# stonyman-breakout-adc.net
KiCad netlist of a schematic drawn in EAGLE
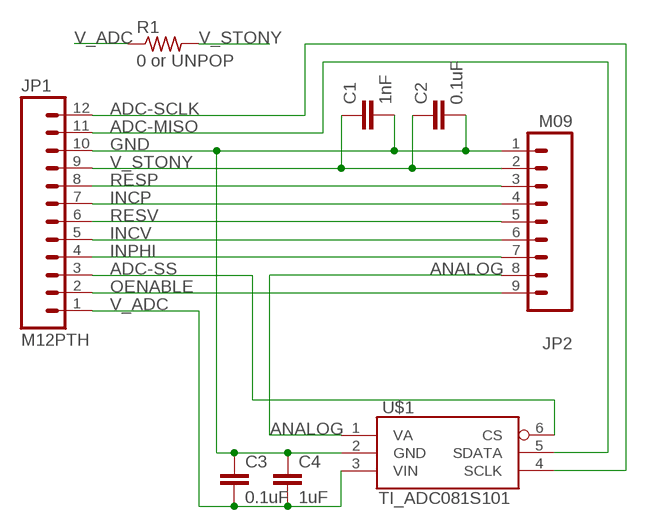
[diagram p0: schematic, sheet 1]

(export (version "E")
  (design (tool "Eeschema 10.0.6"))
  (components
    (comp (ref "C1")
      (value "1nF")
      (footprint "eagle-import:C0603")
      (libsource (lib "eagle-import") (part "C-EUC0603"))
    )
    (comp (ref "C2")
      (value "0.1uF")
      (footprint "eagle-import:C0603")
      (libsource (lib "eagle-import") (part "C-EUC0603"))
    )
    (comp (ref "C3")
      (value "0.1uF")
      (footprint "eagle-import:C0603")
      (libsource (lib "eagle-import") (part "C-EUC0603"))
    )
    (comp (ref "C4")
      (value "1uF")
      (footprint "eagle-import:C0603")
      (libsource (lib "eagle-import") (part "C-EUC0603"))
    )
    (comp (ref "JP1")
      (value "M12PTH")
      (footprint "eagle-import:1X12")
      (libsource (lib "eagle-import") (part "M12PTH"))
    )
    (comp (ref "JP2")
      (value "M09")
      (footprint "eagle-import:1X09")
      (libsource (lib "eagle-import") (part "M09"))
    )
    (comp (ref "R1")
      (value "0 or UNPOP")
      (footprint "eagle-import:R0603")
      (libsource (lib "eagle-import") (part "R-US_R0603"))
    )
    (comp (ref "U$1")
      (value "TI_ADC081S101")
      (footprint "eagle-import:SOT23-6")
      (libsource (lib "eagle-import") (part "TI_ADC081S101"))
    )
  )
  (nets
    (net (code "1") (name "/ADC-MISO") (class "Default")
      (node (ref "JP1") (pin "11") (pinfunction "11_11") (pintype "passive"))
      (node (ref "U$1") (pin "5") (pinfunction "SDATA_5") (pintype "bidirectional"))
    )
    (net (code "2") (name "/ADC-SCLK") (class "Default")
      (node (ref "JP1") (pin "12") (pinfunction "12_12") (pintype "passive"))
      (node (ref "U$1") (pin "4") (pinfunction "SCLK_4") (pintype "bidirectional"))
    )
    (net (code "3") (name "/ADC-SS") (class "Default")
      (node (ref "JP1") (pin "3") (pinfunction "3_3") (pintype "passive"))
      (node (ref "U$1") (pin "6") (pinfunction "CS_6") (pintype "bidirectional"))
    )
    (net (code "4") (name "/ANALOG") (class "Default")
      (node (ref "JP2") (pin "8") (pinfunction "8_8") (pintype "passive"))
      (node (ref "U$1") (pin "1") (pinfunction "VA_1") (pintype "bidirectional"))
    )
    (net (code "5") (name "/GND") (class "Default")
      (node (ref "C1") (pin "2") (pinfunction "2_2") (pintype "passive"))
      (node (ref "C2") (pin "2") (pinfunction "2_2") (pintype "passive"))
      (node (ref "C3") (pin "1") (pinfunction "1_1") (pintype "passive"))
      (node (ref "C4") (pin "1") (pinfunction "1_1") (pintype "passive"))
      (node (ref "JP1") (pin "10") (pinfunction "10_10") (pintype "passive"))
      (node (ref "JP2") (pin "1") (pinfunction "1_1") (pintype "passive"))
      (node (ref "U$1") (pin "2") (pinfunction "GND_2") (pintype "bidirectional"))
    )
    (net (code "6") (name "/INCP") (class "Default")
      (node (ref "JP1") (pin "7") (pinfunction "7_7") (pintype "passive"))
      (node (ref "JP2") (pin "4") (pinfunction "4_4") (pintype "passive"))
    )
    (net (code "7") (name "/INCV") (class "Default")
      (node (ref "JP1") (pin "5") (pinfunction "5_5") (pintype "passive"))
      (node (ref "JP2") (pin "6") (pinfunction "6_6") (pintype "passive"))
    )
    (net (code "8") (name "/INPHI") (class "Default")
      (node (ref "JP1") (pin "4") (pinfunction "4_4") (pintype "passive"))
      (node (ref "JP2") (pin "7") (pinfunction "7_7") (pintype "passive"))
    )
    (net (code "9") (name "/OENABLE") (class "Default")
      (node (ref "JP1") (pin "2") (pinfunction "2_2") (pintype "passive"))
      (node (ref "JP2") (pin "9") (pinfunction "9_9") (pintype "passive"))
    )
    (net (code "10") (name "/RESP") (class "Default")
      (node (ref "JP1") (pin "8") (pinfunction "8_8") (pintype "passive"))
      (node (ref "JP2") (pin "3") (pinfunction "3_3") (pintype "passive"))
    )
    (net (code "11") (name "/RESV") (class "Default")
      (node (ref "JP1") (pin "6") (pinfunction "6_6") (pintype "passive"))
      (node (ref "JP2") (pin "5") (pinfunction "5_5") (pintype "passive"))
    )
    (net (code "12") (name "/V_ADC") (class "Default")
      (node (ref "C3") (pin "2") (pinfunction "2_2") (pintype "passive"))
      (node (ref "C4") (pin "2") (pinfunction "2_2") (pintype "passive"))
      (node (ref "JP1") (pin "1") (pinfunction "1_1") (pintype "passive"))
      (node (ref "R1") (pin "1") (pinfunction "1_1") (pintype "passive"))
      (node (ref "U$1") (pin "3") (pinfunction "VIN_3") (pintype "bidirectional"))
    )
    (net (code "13") (name "/V_STONY") (class "Default")
      (node (ref "C1") (pin "1") (pinfunction "1_1") (pintype "passive"))
      (node (ref "C2") (pin "1") (pinfunction "1_1") (pintype "passive"))
      (node (ref "JP1") (pin "9") (pinfunction "9_9") (pintype "passive"))
      (node (ref "JP2") (pin "2") (pinfunction "2_2") (pintype "passive"))
      (node (ref "R1") (pin "2") (pinfunction "2_2") (pintype "passive"))
    )
  )
)
